# FlatLamp.net
KiCad netlist of a schematic drawn in Altium Designer
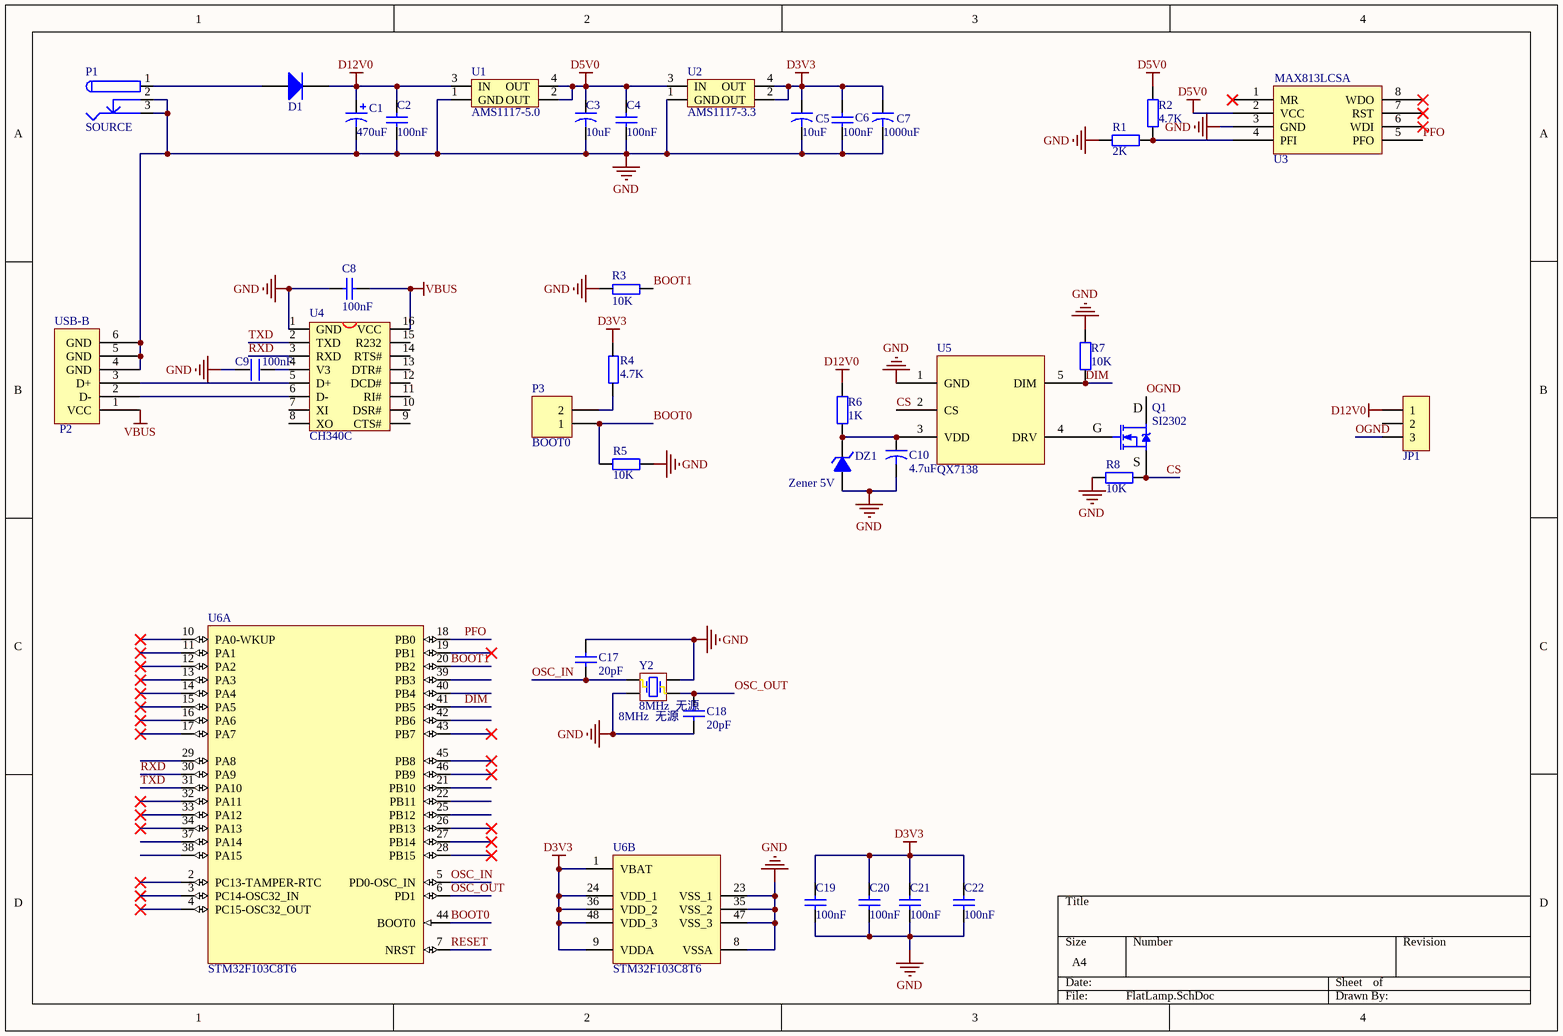
[diagram p0: FlatLamp.SchDoc]

(export (version "E")
  (design (tool "Eeschema 10.0.6"))
  (components
    (comp (ref "C1")
      (value "470uF")
      (footprint "16V/470U(CD10X10D5)")
      (description "470UF      16V      CD10X10D5")
      (libsource (lib "平台原理图symbol图库V1.0") (part "C470UF016S"))
    )
    (comp (ref "C2")
      (value "100nF")
      (footprint "0603C")
      (description "Capacitor")
      (fields (field (name "PUBLISHER") "Altium Limited"))
      (libsource (lib "Crazy_PCB") (part "Cap"))
    )
    (comp (ref "C3")
      (value "10uF")
      (footprint "3216")
      (fields (field (name "VAULE") "10uF"))
      (libsource (lib "Crazy_PCB") (part "CAP2"))
    )
    (comp (ref "C4")
      (value "100nF")
      (footprint "0603C")
      (description "Capacitor")
      (fields (field (name "PUBLISHER") "Altium Limited"))
      (libsource (lib "Crazy_PCB") (part "Cap"))
    )
    (comp (ref "C5")
      (value "10uF")
      (footprint "3216")
      (fields (field (name "VAULE") "10uF"))
      (libsource (lib "Crazy_PCB") (part "CAP2"))
    )
    (comp (ref "C6")
      (value "100nF")
      (footprint "0603C")
      (description "Capacitor")
      (fields (field (name "PUBLISHER") "Altium Limited"))
      (libsource (lib "Crazy_PCB") (part "Cap"))
    )
    (comp (ref "C7")
      (value "1000uF")
      (footprint "16V/470U(CD10X10D5)")
      (fields (field (name "VAULE") "1000uF"))
      (libsource (lib "Crazy_PCB") (part "CAP2"))
    )
    (comp (ref "C8")
      (value "100nF")
      (footprint "0603C")
      (description "Capacitor")
      (fields (field (name "PUBLISHER") "Altium Limited"))
      (libsource (lib "Crazy_PCB") (part "Cap"))
    )
    (comp (ref "C9")
      (value "100nF")
      (footprint "0603C")
      (libsource (lib "WarShip V3 STM32103封装库") (part "C"))
    )
    (comp (ref "C10")
      (value "4.7uF")
      (footprint "3216")
      (fields (field (name "VAULE") "4.7uF"))
      (libsource (lib "Crazy_PCB") (part "CAP2"))
    )
    (comp (ref "C17")
      (value "20pF")
      (footprint "0603C")
      (description "Capacitor")
      (fields (field (name "PUBLISHER") "Altium Limited"))
      (libsource (lib "JL_SCH") (part "Cap"))
    )
    (comp (ref "C18")
      (value "20pF")
      (footprint "0603C")
      (description "Capacitor")
      (fields (field (name "PUBLISHER") "Altium Limited"))
      (libsource (lib "JL_SCH") (part "Cap"))
    )
    (comp (ref "C19")
      (value "100nF")
      (footprint "0603C")
      (description "Capacitor")
      (fields (field (name "PUBLISHER") "Altium Limited"))
      (libsource (lib "Crazy_PCB") (part "Cap"))
    )
    (comp (ref "C20")
      (value "100nF")
      (footprint "0603C")
      (description "Capacitor")
      (fields (field (name "PUBLISHER") "Altium Limited"))
      (libsource (lib "Crazy_PCB") (part "Cap"))
    )
    (comp (ref "C21")
      (value "100nF")
      (footprint "0603C")
      (description "Capacitor")
      (fields (field (name "PUBLISHER") "Altium Limited"))
      (libsource (lib "Crazy_PCB") (part "Cap"))
    )
    (comp (ref "C22")
      (value "100nF")
      (footprint "0603C")
      (description "Capacitor")
      (fields (field (name "PUBLISHER") "Altium Limited"))
      (libsource (lib "Crazy_PCB") (part "Cap"))
    )
    (comp (ref "D1")
      (value "M7")
      (footprint "DO-214AC")
      (description "High Conductance Fast Diode")
      (fields (field (name "PUBLISHER") "Altium Limited"))
      (libsource (lib "Crazy_PCB") (part "Diode"))
    )
    (comp (ref "DZ1")
      (value "Zener 5V")
      (footprint "SOD-323")
      (description "12V/0.5W稳压管")
      (fields (field (name "版权归属") "源创客"))
      (libsource (lib "8.1   - 二极管-整流桥") (part "1N4106"))
    )
    (comp (ref "JP1")
      (value "HDR-1X3")
      (footprint "HDR2.54-LI-3P")
      (description "3P接插件")
      (fields (field (name "版权归属") "源创客"))
      (libsource (lib "4.5   - 接插件-脚距2.54") (part "Header 3"))
    )
    (comp (ref "P1")
      (value "SOURCE")
      (footprint "DC_5.5MM")
      (fields (field (name "PUBLISHER") "Altium Limited"))
      (libsource (lib "Crazy_PCB") (part "SOURCE"))
    )
    (comp (ref "P2") (value "USB-B") (footprint "USB-B") (libsource (lib "DX") (part "USB-B")))
    (comp (ref "P3")
      (value "BOOT0")
      (footprint "HDR1X2")
      (description "Header, 2-Pin")
      (fields (field (name "PUBLISHER") "Altium Limited"))
      (libsource (lib "Miscellaneous Connectors") (part "MHDR1X2"))
    )
    (comp (ref "Q1")
      (value "SI2302")
      (footprint "SOT23-3L")
      (description "N沟道场效应管")
      (fields (field (name "版权归属") "源创客"))
      (libsource (lib "6.1   - 场效应管-可控硅") (part "SI2302"))
    )
    (comp (ref "R1")
      (value "2K")
      (footprint "0603R")
      (description "Resistor")
      (fields (field (name "PUBLISHER") "Altium Limited"))
      (libsource (lib "Crazy_PCB") (part "RES"))
    )
    (comp (ref "R2")
      (value "4.7K")
      (footprint "0603R")
      (description "Resistor")
      (fields (field (name "PUBLISHER") "Altium Limited"))
      (libsource (lib "") (part "RES_3"))
    )
    (comp (ref "R3") (value "10K") (footprint "0603R") (libsource (lib "WarShip V3 STM32103封装库") (part "R")))
    (comp (ref "R4") (value "4.7K") (footprint "0603R") (libsource (lib "WarShip V3 STM32103封装库") (part "R")))
    (comp (ref "R5")
      (value "10K")
      (footprint "0603R")
      (description "Resistor")
      (fields (field (name "PUBLISHER") "Altium Limited"))
      (libsource (lib "") (part "RES_1"))
    )
    (comp (ref "R6")
      (value "1K")
      (footprint "0603R")
      (description "Resistor")
      (fields (field (name "PUBLISHER") "Altium Limited"))
      (libsource (lib "") (part "RES_2"))
    )
    (comp (ref "R7")
      (value "10K")
      (footprint "0603R")
      (description "Resistor")
      (fields (field (name "PUBLISHER") "Altium Limited"))
      (libsource (lib "") (part "RES_2"))
    )
    (comp (ref "R8")
      (value "10K")
      (footprint "1206")
      (description "Resistor")
      (fields (field (name "PUBLISHER") "Altium Limited"))
      (libsource (lib "Crazy_PCB") (part "RES"))
    )
    (comp (ref "U1")
      (value "AMS1117-5.0")
      (footprint "SOT223")
      (libsource (lib "MiniSTM32 V3.0封装库") (part "AMS1117"))
    )
    (comp (ref "U2")
      (value "AMS1117-3.3")
      (footprint "SOT223")
      (libsource (lib "MiniSTM32 V3.0封装库") (part "AMS1117"))
    )
    (comp (ref "U3") (value "MAX813LCSA") (footprint "SOP-8") (libsource (lib "DX") (part "MAX813L")))
    (comp (ref "U4")
      (value "CH340C")
      (footprint "SO-16")
      (description "USB2UART")
      (libsource (lib "WarShip V3 STM32103封装库") (part "CH340G"))
    )
    (comp (ref "U5") (value "QX7138") (footprint "SOT23-5M") (libsource (lib "SS") (part "QX7138")))
    (comp (ref "U6")
      (value "STM32F103C8T6")
      (footprint "LQFP48_N")
      (libsource (lib "STMicroelectronics STM32 F1") (part "STM32F103C8T6"))
    )
    (comp (ref "Y2")
      (value "8MHz  无源")
      (footprint "X3225")
      (description "Crystal Oscillator")
      (fields (field (name "ALTIUM_VALUE") "8MHz  无源") (field (name "PUBLISHER") "Altium Limited"))
      (libsource (lib "JL_SCH") (part "XTAL_1"))
    )
  )
  (nets
    (net (code "1") (name "/BOOT0") (class "Default")
      (node (ref "P3") (pin "1") (pinfunction "1_1") (pintype "passive"))
      (node (ref "R5") (pin "1") (pinfunction "1_1") (pintype "passive"))
      (node (ref "U6") (pin "44") (pinfunction "BOOT0_44") (pintype "input"))
    )
    (net (code "2") (name "/BOOT1") (class "Default")
      (node (ref "R3") (pin "2") (pintype "passive"))
      (node (ref "U6") (pin "20") (pinfunction "PB2_20") (pintype "bidirectional"))
    )
    (net (code "3") (name "/CS") (class "Default")
      (node (ref "Q1") (pin "2") (pinfunction "S_2") (pintype "passive"))
      (node (ref "R8") (pin "1") (pinfunction "1_1") (pintype "passive"))
      (node (ref "U5") (pin "2") (pinfunction "CS_2") (pintype "passive"))
    )
    (net (code "4") (name "/DIM") (class "Default")
      (node (ref "R7") (pin "2") (pinfunction "2_2") (pintype "passive"))
      (node (ref "U5") (pin "5") (pinfunction "DIM_5") (pintype "passive"))
      (node (ref "U6") (pin "41") (pinfunction "PB5_41") (pintype "bidirectional"))
    )
    (net (code "5") (name "/OGND") (class "Default")
      (node (ref "JP1") (pin "3") (pinfunction "3_3") (pintype "passive"))
      (node (ref "Q1") (pin "3") (pinfunction "D_3") (pintype "passive"))
    )
    (net (code "6") (name "/OSC_IN") (class "Default")
      (node (ref "C17") (pin "1") (pinfunction "1_1") (pintype "passive"))
      (node (ref "U6") (pin "5") (pinfunction "PD0-OSC_IN_5") (pintype "bidirectional"))
      (node (ref "Y2") (pin "1") (pinfunction "OSC1_1") (pintype "passive"))
    )
    (net (code "7") (name "/OSC_OUT") (class "Default")
      (node (ref "C18") (pin "1") (pinfunction "1_1") (pintype "passive"))
      (node (ref "U6") (pin "6") (pinfunction "PD1_6") (pintype "bidirectional"))
      (node (ref "Y2") (pin "3") (pinfunction "OSC2_3") (pintype "passive"))
    )
    (net (code "8") (name "/PFO") (class "Default")
      (node (ref "U3") (pin "5") (pinfunction "PFO_5") (pintype "passive"))
      (node (ref "U6") (pin "18") (pinfunction "PB0_18") (pintype "bidirectional"))
    )
    (net (code "9") (name "/RESET") (class "Default")
      (node (ref "U6") (pin "7") (pinfunction "NRST_7") (pintype "bidirectional"))
    )
    (net (code "10") (name "/RXD") (class "Default")
      (node (ref "U4") (pin "3") (pinfunction "RXD_3") (pintype "passive"))
      (node (ref "U6") (pin "30") (pinfunction "PA9_30") (pintype "bidirectional"))
    )
    (net (code "11") (name "/TXD") (class "Default")
      (node (ref "U4") (pin "2") (pinfunction "TXD_2") (pintype "passive"))
      (node (ref "U6") (pin "31") (pinfunction "PA10_31") (pintype "bidirectional"))
    )
    (net (code "12") (name "D3V3") (class "Default")
      (node (ref "C19") (pin "2") (pinfunction "2_2") (pintype "passive"))
      (node (ref "C20") (pin "2") (pinfunction "2_2") (pintype "passive"))
      (node (ref "C21") (pin "2") (pinfunction "2_2") (pintype "passive"))
      (node (ref "C22") (pin "2") (pinfunction "2_2") (pintype "passive"))
      (node (ref "C5") (pin "1") (pinfunction "1_1") (pintype "passive"))
      (node (ref "C6") (pin "2") (pinfunction "2_2") (pintype "passive"))
      (node (ref "C7") (pin "1") (pinfunction "1_1") (pintype "passive"))
      (node (ref "R4") (pin "2") (pintype "passive"))
      (node (ref "U2") (pin "2") (pinfunction "OUT_2") (pintype "passive"))
      (node (ref "U2") (pin "4") (pinfunction "OUT_4") (pintype "passive"))
      (node (ref "U6") (pin "1") (pinfunction "VBAT_1") (pintype "power_in"))
      (node (ref "U6") (pin "24") (pinfunction "VDD_1_24") (pintype "power_in"))
      (node (ref "U6") (pin "36") (pinfunction "VDD_2_36") (pintype "power_in"))
      (node (ref "U6") (pin "48") (pinfunction "VDD_3_48") (pintype "power_in"))
      (node (ref "U6") (pin "9") (pinfunction "VDDA_9") (pintype "power_in"))
    )
    (net (code "13") (name "D5V0") (class "Default")
      (node (ref "C3") (pin "1") (pinfunction "1_1") (pintype "passive"))
      (node (ref "C4") (pin "2") (pinfunction "2_2") (pintype "passive"))
      (node (ref "R2") (pin "2") (pinfunction "2_2") (pintype "passive"))
      (node (ref "U1") (pin "2") (pinfunction "OUT_2") (pintype "passive"))
      (node (ref "U1") (pin "4") (pinfunction "OUT_4") (pintype "passive"))
      (node (ref "U2") (pin "3") (pinfunction "IN_3") (pintype "passive"))
      (node (ref "U3") (pin "2") (pinfunction "VCC_2") (pintype "passive"))
    )
    (net (code "14") (name "D12V0") (class "Default")
      (node (ref "C1") (pin "1") (pinfunction "1_1") (pintype "passive"))
      (node (ref "C2") (pin "2") (pinfunction "2_2") (pintype "passive"))
      (node (ref "D1") (pin "2") (pinfunction "K_2") (pintype "passive"))
      (node (ref "JP1") (pin "1") (pinfunction "1_1") (pintype "passive"))
      (node (ref "R6") (pin "1") (pinfunction "1_1") (pintype "passive"))
      (node (ref "U1") (pin "3") (pinfunction "IN_3") (pintype "passive"))
    )
    (net (code "15") (name "GND") (class "Default")
      (node (ref "C1") (pin "2") (pinfunction "2_2") (pintype "passive"))
      (node (ref "C10") (pin "2") (pinfunction "2_2") (pintype "passive"))
      (node (ref "C17") (pin "2") (pinfunction "2_2") (pintype "passive"))
      (node (ref "C18") (pin "2") (pinfunction "2_2") (pintype "passive"))
      (node (ref "C19") (pin "1") (pinfunction "1_1") (pintype "passive"))
      (node (ref "C2") (pin "1") (pinfunction "1_1") (pintype "passive"))
      (node (ref "C20") (pin "1") (pinfunction "1_1") (pintype "passive"))
      (node (ref "C21") (pin "1") (pinfunction "1_1") (pintype "passive"))
      (node (ref "C22") (pin "1") (pinfunction "1_1") (pintype "passive"))
      (node (ref "C3") (pin "2") (pinfunction "2_2") (pintype "passive"))
      (node (ref "C4") (pin "1") (pinfunction "1_1") (pintype "passive"))
      (node (ref "C5") (pin "2") (pinfunction "2_2") (pintype "passive"))
      (node (ref "C6") (pin "1") (pinfunction "1_1") (pintype "passive"))
      (node (ref "C7") (pin "2") (pinfunction "2_2") (pintype "passive"))
      (node (ref "C8") (pin "1") (pinfunction "1_1") (pintype "passive"))
      (node (ref "C9") (pin "1") (pintype "passive"))
      (node (ref "DZ1") (pin "1") (pinfunction "A_1") (pintype "passive"))
      (node (ref "P1") (pin "2") (pinfunction "2_2") (pintype "power_in"))
      (node (ref "P1") (pin "3") (pinfunction "3_3") (pintype "power_in"))
      (node (ref "P2") (pin "4") (pinfunction "GND_4") (pintype "passive"))
      (node (ref "P2") (pin "5") (pinfunction "GND_5") (pintype "passive"))
      (node (ref "P2") (pin "6") (pinfunction "GND_6") (pintype "passive"))
      (node (ref "R1") (pin "2") (pinfunction "2_2") (pintype "passive"))
      (node (ref "R3") (pin "1") (pintype "passive"))
      (node (ref "R5") (pin "2") (pinfunction "2_2") (pintype "passive"))
      (node (ref "R7") (pin "1") (pinfunction "1_1") (pintype "passive"))
      (node (ref "R8") (pin "2") (pinfunction "2_2") (pintype "passive"))
      (node (ref "U1") (pin "1") (pinfunction "GND_1") (pintype "passive"))
      (node (ref "U2") (pin "1") (pinfunction "GND_1") (pintype "passive"))
      (node (ref "U3") (pin "3") (pinfunction "GND_3") (pintype "passive"))
      (node (ref "U4") (pin "1") (pinfunction "GND_1") (pintype "passive"))
      (node (ref "U5") (pin "1") (pinfunction "GND_1") (pintype "passive"))
      (node (ref "U6") (pin "23") (pinfunction "VSS_1_23") (pintype "power_in"))
      (node (ref "U6") (pin "35") (pinfunction "VSS_2_35") (pintype "power_in"))
      (node (ref "U6") (pin "47") (pinfunction "VSS_3_47") (pintype "power_in"))
      (node (ref "U6") (pin "8") (pinfunction "VSSA_8") (pintype "power_in"))
      (node (ref "Y2") (pin "2") (pinfunction "NA_2") (pintype "passive"))
      (node (ref "Y2") (pin "4") (pinfunction "NA_4") (pintype "passive"))
    )
    (net (code "16") (name "Net-(D1-A)") (class "Default")
      (node (ref "D1") (pin "1") (pinfunction "A_1") (pintype "passive"))
      (node (ref "P1") (pin "1") (pinfunction "1_1") (pintype "power_in"))
    )
    (net (code "17") (name "Net-(DZ1-K)") (class "Default")
      (node (ref "C10") (pin "1") (pinfunction "1_1") (pintype "passive"))
      (node (ref "DZ1") (pin "2") (pinfunction "K_2") (pintype "passive"))
      (node (ref "R6") (pin "2") (pinfunction "2_2") (pintype "passive"))
      (node (ref "U5") (pin "3") (pinfunction "VDD_3") (pintype "passive"))
    )
    (net (code "18") (name "Net-(P2-D+)") (class "Default")
      (node (ref "P2") (pin "3") (pinfunction "D+_3") (pintype "passive"))
      (node (ref "U4") (pin "5") (pinfunction "D+_5") (pintype "passive"))
    )
    (net (code "19") (name "Net-(P2-D-)") (class "Default")
      (node (ref "P2") (pin "2") (pinfunction "D-_2") (pintype "passive"))
      (node (ref "U4") (pin "6") (pinfunction "D-_6") (pintype "passive"))
    )
    (net (code "20") (name "Net-(P3-Pad2)") (class "Default")
      (node (ref "P3") (pin "2") (pinfunction "2_2") (pintype "passive"))
      (node (ref "R4") (pin "1") (pintype "passive"))
    )
    (net (code "21") (name "Net-(Q1-G)") (class "Default")
      (node (ref "Q1") (pin "1") (pinfunction "G_1") (pintype "passive"))
      (node (ref "U5") (pin "4") (pinfunction "DRV_4") (pintype "passive"))
    )
    (net (code "22") (name "Net-(U3-PFI)") (class "Default")
      (node (ref "R1") (pin "1") (pinfunction "1_1") (pintype "passive"))
      (node (ref "R2") (pin "1") (pinfunction "1_1") (pintype "passive"))
      (node (ref "U3") (pin "4") (pinfunction "PFI_4") (pintype "passive"))
    )
    (net (code "23") (name "Net-(U4-V3)") (class "Default")
      (node (ref "C9") (pin "2") (pintype "passive"))
      (node (ref "U4") (pin "4") (pinfunction "V3_4") (pintype "passive"))
    )
    (net (code "24") (name "VBUS") (class "Default")
      (node (ref "C8") (pin "2") (pinfunction "2_2") (pintype "passive"))
      (node (ref "P2") (pin "1") (pinfunction "VCC_1") (pintype "passive"))
      (node (ref "U4") (pin "16") (pinfunction "VCC_16") (pintype "passive"))
    )
    (net (code "25") (name "unconnected-(JP1-Pad2)") (class "Default")
      (node (ref "JP1") (pin "2") (pinfunction "2_2") (pintype "passive"))
    )
    (net (code "26") (name "unconnected-(U3-MR-Pad1)") (class "Default")
      (node (ref "U3") (pin "1") (pinfunction "MR_1") (pintype "passive+no_connect"))
    )
    (net (code "27") (name "unconnected-(U3-RST-Pad7)") (class "Default")
      (node (ref "U3") (pin "7") (pinfunction "RST_7") (pintype "passive+no_connect"))
    )
    (net (code "28") (name "unconnected-(U3-WDI-Pad6)") (class "Default")
      (node (ref "U3") (pin "6") (pinfunction "WDI_6") (pintype "passive+no_connect"))
    )
    (net (code "29") (name "unconnected-(U3-WDO-Pad8)") (class "Default")
      (node (ref "U3") (pin "8") (pinfunction "WDO_8") (pintype "passive+no_connect"))
    )
    (net (code "30") (name "unconnected-(U4-CTS#-Pad9)") (class "Default")
      (node (ref "U4") (pin "9") (pinfunction "CTS#_9") (pintype "passive"))
    )
    (net (code "31") (name "unconnected-(U4-DCD#-Pad12)") (class "Default")
      (node (ref "U4") (pin "12") (pinfunction "DCD#_12") (pintype "passive"))
    )
    (net (code "32") (name "unconnected-(U4-DSR#-Pad10)") (class "Default")
      (node (ref "U4") (pin "10") (pinfunction "DSR#_10") (pintype "passive"))
    )
    (net (code "33") (name "unconnected-(U4-DTR#-Pad13)") (class "Default")
      (node (ref "U4") (pin "13") (pinfunction "DTR#_13") (pintype "passive"))
    )
    (net (code "34") (name "unconnected-(U4-R232-Pad15)") (class "Default")
      (node (ref "U4") (pin "15") (pinfunction "R232_15") (pintype "passive"))
    )
    (net (code "35") (name "unconnected-(U4-RI#-Pad11)") (class "Default")
      (node (ref "U4") (pin "11") (pinfunction "RI#_11") (pintype "passive"))
    )
    (net (code "36") (name "unconnected-(U4-RTS#-Pad14)") (class "Default")
      (node (ref "U4") (pin "14") (pinfunction "RTS#_14") (pintype "passive"))
    )
    (net (code "37") (name "unconnected-(U4-XI-Pad7)") (class "Default")
      (node (ref "U4") (pin "7") (pinfunction "XI_7") (pintype "passive"))
    )
    (net (code "38") (name "unconnected-(U4-XO-Pad8)") (class "Default")
      (node (ref "U4") (pin "8") (pinfunction "XO_8") (pintype "passive"))
    )
    (net (code "39") (name "unconnected-(U6A-PA0-WKUP-Pad10)") (class "Default")
      (node (ref "U6") (pin "10") (pinfunction "PA0-WKUP_10") (pintype "bidirectional+no_connect"))
    )
    (net (code "40") (name "unconnected-(U6A-PA1-Pad11)") (class "Default")
      (node (ref "U6") (pin "11") (pinfunction "PA1_11") (pintype "bidirectional+no_connect"))
    )
    (net (code "41") (name "unconnected-(U6A-PA2-Pad12)") (class "Default")
      (node (ref "U6") (pin "12") (pinfunction "PA2_12") (pintype "bidirectional+no_connect"))
    )
    (net (code "42") (name "unconnected-(U6A-PA3-Pad13)") (class "Default")
      (node (ref "U6") (pin "13") (pinfunction "PA3_13") (pintype "bidirectional+no_connect"))
    )
    (net (code "43") (name "unconnected-(U6A-PA4-Pad14)") (class "Default")
      (node (ref "U6") (pin "14") (pinfunction "PA4_14") (pintype "bidirectional+no_connect"))
    )
    (net (code "44") (name "unconnected-(U6A-PA5-Pad15)") (class "Default")
      (node (ref "U6") (pin "15") (pinfunction "PA5_15") (pintype "bidirectional+no_connect"))
    )
    (net (code "45") (name "unconnected-(U6A-PA6-Pad16)") (class "Default")
      (node (ref "U6") (pin "16") (pinfunction "PA6_16") (pintype "bidirectional+no_connect"))
    )
    (net (code "46") (name "unconnected-(U6A-PA7-Pad17)") (class "Default")
      (node (ref "U6") (pin "17") (pinfunction "PA7_17") (pintype "bidirectional+no_connect"))
    )
    (net (code "47") (name "unconnected-(U6A-PA8-Pad29)") (class "Default")
      (node (ref "U6") (pin "29") (pinfunction "PA8_29") (pintype "bidirectional"))
    )
    (net (code "48") (name "unconnected-(U6A-PA11-Pad32)") (class "Default")
      (node (ref "U6") (pin "32") (pinfunction "PA11_32") (pintype "bidirectional+no_connect"))
    )
    (net (code "49") (name "unconnected-(U6A-PA12-Pad33)") (class "Default")
      (node (ref "U6") (pin "33") (pinfunction "PA12_33") (pintype "bidirectional+no_connect"))
    )
    (net (code "50") (name "unconnected-(U6A-PA13-Pad34)") (class "Default")
      (node (ref "U6") (pin "34") (pinfunction "PA13_34") (pintype "bidirectional+no_connect"))
    )
    (net (code "51") (name "unconnected-(U6A-PA14-Pad37)") (class "Default")
      (node (ref "U6") (pin "37") (pinfunction "PA14_37") (pintype "bidirectional"))
    )
    (net (code "52") (name "unconnected-(U6A-PA15-Pad38)") (class "Default")
      (node (ref "U6") (pin "38") (pinfunction "PA15_38") (pintype "bidirectional"))
    )
    (net (code "53") (name "unconnected-(U6A-PB1-Pad19)") (class "Default")
      (node (ref "U6") (pin "19") (pinfunction "PB1_19") (pintype "bidirectional+no_connect"))
    )
    (net (code "54") (name "unconnected-(U6A-PB3-Pad39)") (class "Default")
      (node (ref "U6") (pin "39") (pinfunction "PB3_39") (pintype "bidirectional"))
    )
    (net (code "55") (name "unconnected-(U6A-PB4-Pad40)") (class "Default")
      (node (ref "U6") (pin "40") (pinfunction "PB4_40") (pintype "bidirectional"))
    )
    (net (code "56") (name "unconnected-(U6A-PB6-Pad42)") (class "Default")
      (node (ref "U6") (pin "42") (pinfunction "PB6_42") (pintype "bidirectional"))
    )
    (net (code "57") (name "unconnected-(U6A-PB7-Pad43)") (class "Default")
      (node (ref "U6") (pin "43") (pinfunction "PB7_43") (pintype "bidirectional+no_connect"))
    )
    (net (code "58") (name "unconnected-(U6A-PB8-Pad45)") (class "Default")
      (node (ref "U6") (pin "45") (pinfunction "PB8_45") (pintype "bidirectional+no_connect"))
    )
    (net (code "59") (name "unconnected-(U6A-PB9-Pad46)") (class "Default")
      (node (ref "U6") (pin "46") (pinfunction "PB9_46") (pintype "bidirectional+no_connect"))
    )
    (net (code "60") (name "unconnected-(U6A-PB10-Pad21)") (class "Default")
      (node (ref "U6") (pin "21") (pinfunction "PB10_21") (pintype "bidirectional"))
    )
    (net (code "61") (name "unconnected-(U6A-PB11-Pad22)") (class "Default")
      (node (ref "U6") (pin "22") (pinfunction "PB11_22") (pintype "bidirectional"))
    )
    (net (code "62") (name "unconnected-(U6A-PB12-Pad25)") (class "Default")
      (node (ref "U6") (pin "25") (pinfunction "PB12_25") (pintype "bidirectional"))
    )
    (net (code "63") (name "unconnected-(U6A-PB13-Pad26)") (class "Default")
      (node (ref "U6") (pin "26") (pinfunction "PB13_26") (pintype "bidirectional+no_connect"))
    )
    (net (code "64") (name "unconnected-(U6A-PB14-Pad27)") (class "Default")
      (node (ref "U6") (pin "27") (pinfunction "PB14_27") (pintype "bidirectional+no_connect"))
    )
    (net (code "65") (name "unconnected-(U6A-PB15-Pad28)") (class "Default")
      (node (ref "U6") (pin "28") (pinfunction "PB15_28") (pintype "bidirectional+no_connect"))
    )
    (net (code "66") (name "unconnected-(U6A-PC13-TAMPER-RTC-Pad2)") (class "Default")
      (node (ref "U6") (pin "2") (pinfunction "PC13-TAMPER-RTC_2") (pintype "bidirectional+no_connect"))
    )
    (net (code "67") (name "unconnected-(U6A-PC14-OSC32_IN-Pad3)") (class "Default")
      (node (ref "U6") (pin "3") (pinfunction "PC14-OSC32_IN_3") (pintype "bidirectional+no_connect"))
    )
    (net (code "68") (name "unconnected-(U6A-PC15-OSC32_OUT-Pad4)") (class "Default")
      (node (ref "U6") (pin "4") (pinfunction "PC15-OSC32_OUT_4") (pintype "bidirectional+no_connect"))
    )
  )
)
